# 4V-12V_-24V_Boost_Converter.net
KiCad netlist of a schematic drawn in Altium Designer
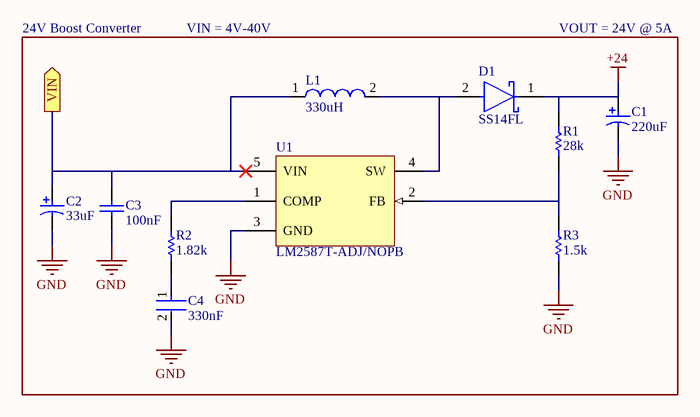
[diagram p0: (4V-12V)-24V Boost Converter.SchDoc]

(export (version "E")
  (design (tool "Eeschema 10.0.6"))
  (components
    (comp (ref "C1")
      (value "220uF")
      (footprint "PNSC-EEE-FK1E221P_N")
      (fields (field (name "MANUFACTURER") "Panasonic"))
      (libsource (lib "Altium Content Vault") (part "CAP-P-2"))
    )
    (comp (ref "C2")
      (value "33uF")
      (footprint "NIC-CAPA2-6.3X5.8_V")
      (fields (field (name "PARTNUMBER") "UUD1V330MCL1GS") (field (name "MANUFACTURER") "Nichicon"))
      (libsource (lib "Altium Content Vault") (part "NIC-CAP-P-2"))
    )
    (comp (ref "C3")
      (value "100nF")
      (footprint "CAPC2013X88X50NL20T25")
      (fields (field (name "PART NUMBER") "C0805C104K5RACTU") (field (name "MANUFACTURER") "Kemet"))
      (libsource (lib "Altium Content Vault") (part "CAP"))
    )
    (comp (ref "C4")
      (value "330nF")
      (footprint "FP-CC0805-0_85-MFG")
      (description "CAP CER 0.33UF 25V X7R 0805")
      (fields
        (field (name "MANUFACTURER") "Yageo")
        (field (name "OCTOPART") "https://octopart.com/cc0805kkx7r8bb334-yageo-24732840")
      )
      (libsource (lib "Altium Content Vault") (part "11868f565c42a9108669ba33697ecf6"))
    )
    (comp (ref "D1")
      (value "SS14FL")
      (footprint "FP-425AD-MFG")
      (description "DIODE SCHOTTKY 40V 1A SOD123F")
      (fields
        (field (name "MANUFACTURER") "ON Semiconductor")
        (field (name "OCTOPART") "https://octopart.com/ss14fl-on+semiconductor-84331601")
      )
      (libsource (lib "Altium Content Vault") (part "c1678fac7984e62e0809fbf79c06691"))
    )
    (comp (ref "L1")
      (value "330uH")
      (footprint "WE-TI-LM-SHLD")
      (description "Shielded Radial Leaded Wire Wound Inductor WE-TIS, L=330 µH")
      (fields (field (name "PARTNUMBER") "744731331") (field (name "MANUFACTURER") "Wuerth Elektronik"))
      (libsource (lib "Altium Content Vault") (part "PAS-IND-INDUCTOR-2"))
    )
    (comp (ref "R1")
      (value "28k")
      (footprint "RESC2013X70X40ML20T20")
      (fields (field (name "PART NUMBER") "ERJ-6ENF2802V") (field (name "MANUFACTURER") "Panasonic"))
      (libsource (lib "Altium Content Vault") (part "RES"))
    )
    (comp (ref "R2")
      (value "1.82k")
      (footprint "RESC2013X60X35ML10T20")
      (fields (field (name "PART NUMBER") "RC0805FR-07182KL") (field (name "MANUFACTURER") "Yageo"))
      (libsource (lib "Altium Content Vault") (part "RES"))
    )
    (comp (ref "R3")
      (value "1.5k")
      (footprint "RESC2013X70X40ML20T20")
      (fields (field (name "MANUFACTURER") "Panasonic") (field (name "PART NUMBER") "ERJ-6ENF1501V"))
      (libsource (lib "Altium Content Vault") (part "RES"))
    )
    (comp (ref "U1")
      (value "LM2587T-ADJ/NOPB")
      (footprint "NDH0005A")
      (description "5A Flyback Regulator, 5-pin TO-220, Pb-Free")
      (fields (field (name "MANUFACTURER") "Texas Instruments"))
      (libsource (lib "Altium Content Vault") (part "PM-SWREG-LM2585T-12"))
    )
  )
  (nets
    (net (code "1") (name "+24") (class "Default")
      (node (ref "C1") (pin "1") (pinfunction "1_1") (pintype "passive"))
      (node (ref "D1") (pin "1") (pinfunction "C_1") (pintype "passive"))
      (node (ref "R1") (pin "2") (pinfunction "2_2") (pintype "passive"))
    )
    (net (code "2") (name "/VIN") (class "Default")
      (node (ref "C2") (pin "1") (pinfunction "1_1") (pintype "passive"))
      (node (ref "C3") (pin "2") (pinfunction "2_2") (pintype "passive"))
      (node (ref "L1") (pin "1") (pinfunction "1_1") (pintype "passive"))
      (node (ref "U1") (pin "5") (pinfunction "VIN_5") (pintype "power_in"))
    )
    (net (code "3") (name "GND") (class "Default")
      (node (ref "C1") (pin "2") (pinfunction "2_2") (pintype "passive"))
      (node (ref "C2") (pin "2") (pinfunction "2_2") (pintype "passive"))
      (node (ref "C3") (pin "1") (pinfunction "1_1") (pintype "passive"))
      (node (ref "C4") (pin "2") (pinfunction "2_2") (pintype "passive"))
      (node (ref "R3") (pin "1") (pinfunction "1_1") (pintype "passive"))
      (node (ref "U1") (pin "3") (pinfunction "GND_3") (pintype "power_in"))
    )
    (net (code "4") (name "Net-(C4-Pad1)") (class "Default")
      (node (ref "C4") (pin "1") (pinfunction "1_1") (pintype "passive"))
      (node (ref "R2") (pin "1") (pinfunction "1_1") (pintype "passive"))
    )
    (net (code "5") (name "Net-(D1-A)") (class "Default")
      (node (ref "D1") (pin "2") (pinfunction "A_2") (pintype "passive"))
      (node (ref "L1") (pin "2") (pinfunction "2_2") (pintype "passive"))
      (node (ref "U1") (pin "4") (pinfunction "SW_4") (pintype "power_in"))
    )
    (net (code "6") (name "Net-(U1-COMP)") (class "Default")
      (node (ref "R2") (pin "2") (pinfunction "2_2") (pintype "passive"))
      (node (ref "U1") (pin "1") (pinfunction "COMP_1") (pintype "passive"))
    )
    (net (code "7") (name "Net-(U1-FB)") (class "Default")
      (node (ref "R1") (pin "1") (pinfunction "1_1") (pintype "passive"))
      (node (ref "R3") (pin "2") (pinfunction "2_2") (pintype "passive"))
      (node (ref "U1") (pin "2") (pinfunction "FB_2") (pintype "input"))
    )
  )
)
